# power_supply.net
KiCad netlist of a schematic drawn in EAGLE
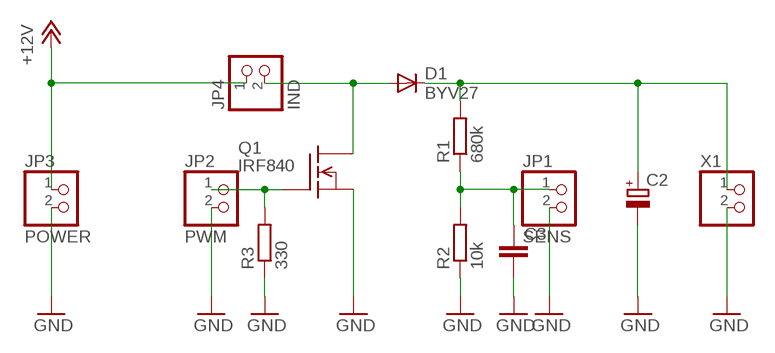
[diagram p0: schematic, sheet 1]

(export (version "E")
  (design (tool "Eeschema 10.0.6"))
  (components
    (comp (ref "C2")
      (value "CPOL-EUE5-10,5")
      (footprint "eagle-import:E5-10,5")
      (libsource (lib "eagle-import") (part "CPOL-EUE5-10,5"))
    )
    (comp (ref "C3")
      (value "C-EU102-043X133")
      (footprint "eagle-import:C102-043X133")
      (libsource (lib "eagle-import") (part "C-EU102-043X133"))
    )
    (comp (ref "D1")
      (value "BYV27")
      (footprint "eagle-import:SOD57")
      (libsource (lib "eagle-import") (part "BYV277"))
    )
    (comp (ref "JP1")
      (value "SENS")
      (footprint "eagle-import:1X02")
      (libsource (lib "eagle-import") (part "PINHD-1X2"))
    )
    (comp (ref "JP2")
      (value "PWM")
      (footprint "eagle-import:1X02")
      (libsource (lib "eagle-import") (part "PINHD-1X2"))
    )
    (comp (ref "JP3")
      (value "POWER")
      (footprint "eagle-import:1X02")
      (libsource (lib "eagle-import") (part "PINHD-1X2"))
    )
    (comp (ref "JP4")
      (value "IND")
      (footprint "eagle-import:1X02")
      (libsource (lib "eagle-import") (part "PINHD-1X2"))
    )
    (comp (ref "Q1")
      (value "IRF840")
      (footprint "eagle-import:TO220-A")
      (libsource (lib "eagle-import") (part "IRF840A"))
    )
    (comp (ref "R1")
      (value "680k")
      (footprint "eagle-import:0207_7")
      (libsource (lib "eagle-import") (part "R-EU_"))
    )
    (comp (ref "R2")
      (value "10k")
      (footprint "eagle-import:0207_7")
      (libsource (lib "eagle-import") (part "R-EU_"))
    )
    (comp (ref "R3")
      (value "330")
      (footprint "eagle-import:0207_7")
      (libsource (lib "eagle-import") (part "R-EU_"))
    )
    (comp (ref "X1")
      (value "W237-102")
      (footprint "eagle-import:W237-102")
      (libsource (lib "eagle-import") (part "W237-102"))
    )
  )
  (nets
    (net (code "1") (name "+12V") (class "Default")
      (node (ref "JP3") (pin "1") (pinfunction "1_1") (pintype "passive"))
      (node (ref "JP4") (pin "1") (pinfunction "1_1") (pintype "passive"))
    )
    (net (code "2") (name "GND") (class "Default")
      (node (ref "C2") (pin "-") (pinfunction "-_-") (pintype "passive"))
      (node (ref "C3") (pin "2") (pinfunction "2_2") (pintype "passive"))
      (node (ref "JP1") (pin "2") (pinfunction "2_2") (pintype "passive"))
      (node (ref "JP2") (pin "2") (pinfunction "2_2") (pintype "passive"))
      (node (ref "JP3") (pin "2") (pinfunction "2_2") (pintype "passive"))
      (node (ref "Q1") (pin "3") (pinfunction "S_3") (pintype "passive"))
      (node (ref "R2") (pin "1") (pinfunction "1_1") (pintype "passive"))
      (node (ref "R3") (pin "1") (pinfunction "1_1") (pintype "passive"))
      (node (ref "X1") (pin "2") (pinfunction "2_2") (pintype "passive"))
    )
    (net (code "3") (name "Net-(C2-Pad+)") (class "Default")
      (node (ref "C2") (pin "+") (pinfunction "+_+") (pintype "passive"))
      (node (ref "D1") (pin "C") (pinfunction "C_C") (pintype "passive"))
      (node (ref "R1") (pin "2") (pinfunction "2_2") (pintype "passive"))
      (node (ref "X1") (pin "1") (pinfunction "1_1") (pintype "passive"))
    )
    (net (code "4") (name "Net-(C3-Pad1)") (class "Default")
      (node (ref "C3") (pin "1") (pinfunction "1_1") (pintype "passive"))
      (node (ref "JP1") (pin "1") (pinfunction "1_1") (pintype "passive"))
      (node (ref "R1") (pin "1") (pinfunction "1_1") (pintype "passive"))
      (node (ref "R2") (pin "2") (pinfunction "2_2") (pintype "passive"))
    )
    (net (code "5") (name "Net-(Q1-D)") (class "Default")
      (node (ref "D1") (pin "A") (pinfunction "A_A") (pintype "passive"))
      (node (ref "JP4") (pin "2") (pinfunction "2_2") (pintype "passive"))
      (node (ref "Q1") (pin "2") (pinfunction "D_2") (pintype "passive"))
    )
    (net (code "6") (name "Net-(Q1-G)") (class "Default")
      (node (ref "JP2") (pin "1") (pinfunction "1_1") (pintype "passive"))
      (node (ref "Q1") (pin "1") (pinfunction "G_1") (pintype "passive"))
      (node (ref "R3") (pin "2") (pinfunction "2_2") (pintype "passive"))
    )
  )
)
